# 1_energy_dist.net
KiCad netlist of a schematic drawn in EAGLE
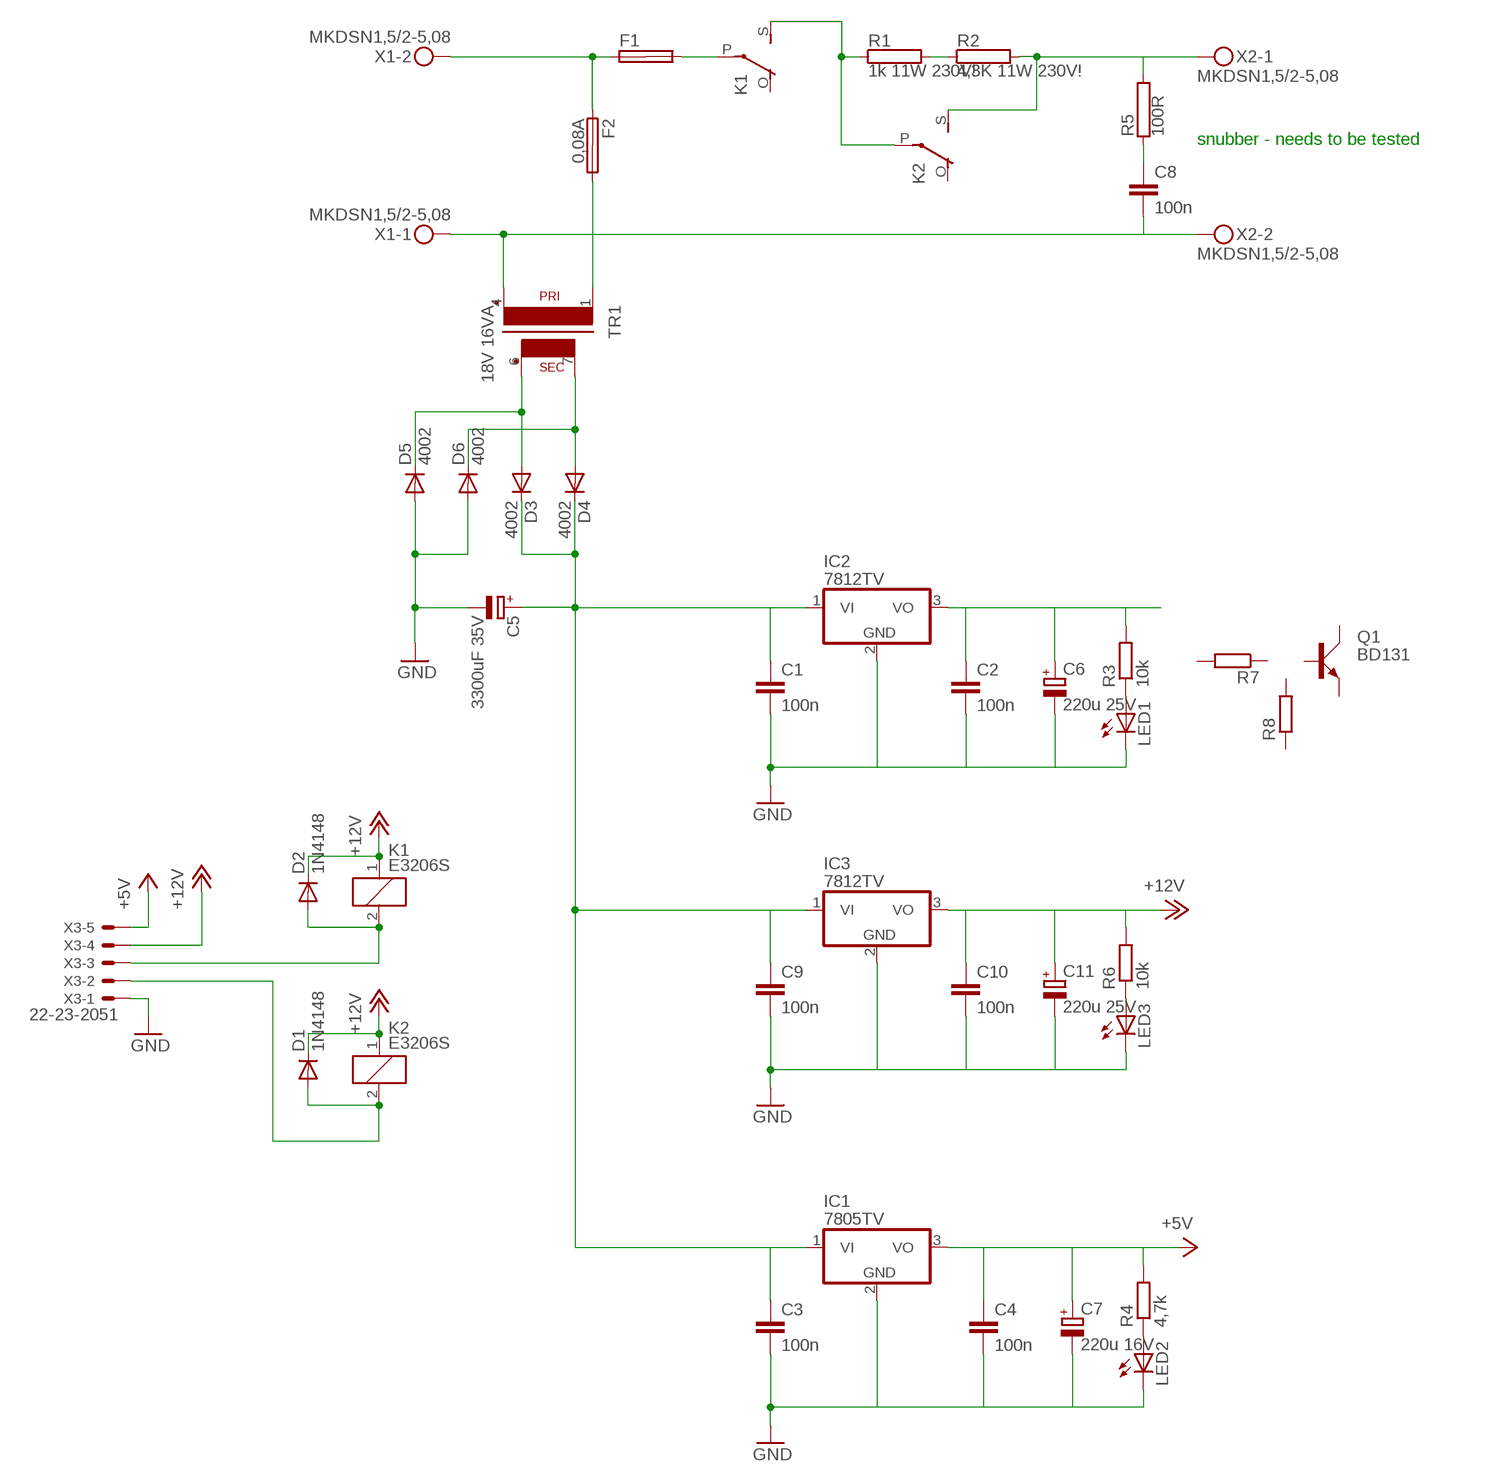
[diagram p0: schematic, sheet 1]

(export (version "E")
  (design (tool "Eeschema 10.0.6"))
  (components
    (comp (ref "C1")
      (value "100n")
      (footprint "eagle-import:C1206")
      (libsource (lib "eagle-import") (part "C-EUC1206"))
    )
    (comp (ref "C2")
      (value "100n")
      (footprint "eagle-import:C1206")
      (libsource (lib "eagle-import") (part "C-EUC1206"))
    )
    (comp (ref "C3")
      (value "100n")
      (footprint "eagle-import:C1206")
      (libsource (lib "eagle-import") (part "C-EUC1206"))
    )
    (comp (ref "C4")
      (value "100n")
      (footprint "eagle-import:C1206")
      (libsource (lib "eagle-import") (part "C-EUC1206"))
    )
    (comp (ref "C5")
      (value "3300uF 35V")
      (footprint "eagle-import:E7,5-16")
      (libsource (lib "eagle-import") (part "CPOL-EUE7.5-16"))
    )
    (comp (ref "C6")
      (value "220u 25V")
      (footprint "eagle-import:E7,5-16")
      (libsource (lib "eagle-import") (part "CPOL-EUE7.5-16"))
    )
    (comp (ref "C7")
      (value "220u 16V")
      (footprint "eagle-import:E7,5-16")
      (libsource (lib "eagle-import") (part "CPOL-EUE7.5-16"))
    )
    (comp (ref "C8")
      (value "100n")
      (footprint "eagle-import:C275-154X316")
      (libsource (lib "eagle-import") (part "C-EU275-154X316"))
    )
    (comp (ref "C9")
      (value "100n")
      (footprint "eagle-import:C1206")
      (libsource (lib "eagle-import") (part "C-EUC1206"))
    )
    (comp (ref "C10")
      (value "100n")
      (footprint "eagle-import:C1206")
      (libsource (lib "eagle-import") (part "C-EUC1206"))
    )
    (comp (ref "C11")
      (value "220u 25V")
      (footprint "eagle-import:E7,5-16")
      (libsource (lib "eagle-import") (part "CPOL-EUE7.5-16"))
    )
    (comp (ref "D1")
      (value "1N4148")
      (footprint "eagle-import:MELF-MLL41")
      (libsource (lib "eagle-import") (part "DIODE-MELF-MLL41"))
    )
    (comp (ref "D2")
      (value "1N4148")
      (footprint "eagle-import:MELF-MLL41")
      (libsource (lib "eagle-import") (part "DIODE-MELF-MLL41"))
    )
    (comp (ref "D3")
      (value "4002")
      (footprint "eagle-import:SOD-123_MINI-SMA")
      (libsource (lib "eagle-import") (part "CGRM400-G2"))
    )
    (comp (ref "D4")
      (value "4002")
      (footprint "eagle-import:SOD-123_MINI-SMA")
      (libsource (lib "eagle-import") (part "CGRM400-G2"))
    )
    (comp (ref "D5")
      (value "4002")
      (footprint "eagle-import:SOD-123_MINI-SMA")
      (libsource (lib "eagle-import") (part "CGRM400-G2"))
    )
    (comp (ref "D6")
      (value "4002")
      (footprint "eagle-import:SOD-123_MINI-SMA")
      (libsource (lib "eagle-import") (part "CGRM400-G2"))
    )
    (comp (ref "F1")
      (value "SH32")
      (footprint "eagle-import:SH32")
      (fields (field (name "MPN") "10207101009"))
      (libsource (lib "eagle-import") (part "SH32"))
    )
    (comp (ref "F2")
      (value "0,08A")
      (footprint "eagle-import:SH32")
      (fields (field (name "MPN") "10207101009"))
      (libsource (lib "eagle-import") (part "SH32"))
    )
    (comp (ref "IC1")
      (value "7805TV")
      (footprint "eagle-import:TO220V")
      (libsource (lib "eagle-import") (part "78TV05"))
    )
    (comp (ref "IC2")
      (value "7812TV")
      (footprint "eagle-import:TO220V")
      (libsource (lib "eagle-import") (part "78TV12"))
    )
    (comp (ref "IC3")
      (value "7812TV")
      (footprint "eagle-import:TO220V")
      (libsource (lib "eagle-import") (part "78TV12"))
    )
    (comp (ref "K1")
      (value "E3206S")
      (footprint "eagle-import:E3206S")
      (libsource (lib "eagle-import") (part "E3206S"))
    )
    (comp (ref "K2")
      (value "E3206S")
      (footprint "eagle-import:E3206S")
      (libsource (lib "eagle-import") (part "E3206S"))
    )
    (comp (ref "LED1")
      (value "LEDCHIPLED_1206")
      (footprint "eagle-import:CHIPLED_1206")
      (libsource (lib "eagle-import") (part "LEDCHIPLED_1206"))
    )
    (comp (ref "LED2")
      (value "LEDCHIPLED_1206")
      (footprint "eagle-import:CHIPLED_1206")
      (libsource (lib "eagle-import") (part "LEDCHIPLED_1206"))
    )
    (comp (ref "LED3")
      (value "LEDCHIPLED_1206")
      (footprint "eagle-import:CHIPLED_1206")
      (libsource (lib "eagle-import") (part "LEDCHIPLED_1206"))
    )
    (comp (ref "Q1")
      (value "BD131")
      (footprint "eagle-import:TO126AV")
      (libsource (lib "eagle-import") (part "BD139"))
    )
    (comp (ref "R1")
      (value "1k 11W 230V!")
      (footprint "eagle-import:KH216-8")
      (libsource (lib "eagle-import") (part "RKH216-8"))
    )
    (comp (ref "R2")
      (value "4,3K 11W 230V!")
      (footprint "eagle-import:KH216-8")
      (libsource (lib "eagle-import") (part "RKH216-8"))
    )
    (comp (ref "R3")
      (value "10k")
      (footprint "eagle-import:M1206")
      (libsource (lib "eagle-import") (part "R-EU_M1206"))
    )
    (comp (ref "R4")
      (value "4,7k")
      (footprint "eagle-import:M1206")
      (libsource (lib "eagle-import") (part "R-EU_M1206"))
    )
    (comp (ref "R5")
      (value "100R")
      (footprint "eagle-import:CA0001")
      (libsource (lib "eagle-import") (part "RCA0001"))
    )
    (comp (ref "R6")
      (value "10k")
      (footprint "eagle-import:M1206")
      (libsource (lib "eagle-import") (part "R-EU_M1206"))
    )
    (comp (ref "R7")
      (value "R-EU_M1206")
      (footprint "eagle-import:M1206")
      (libsource (lib "eagle-import") (part "R-EU_M1206"))
    )
    (comp (ref "R8")
      (value "R-EU_M1206")
      (footprint "eagle-import:M1206")
      (libsource (lib "eagle-import") (part "R-EU_M1206"))
    )
    (comp (ref "TR1")
      (value "18V 16VA")
      (footprint "eagle-import:EE20-1")
      (libsource (lib "eagle-import") (part "EE20-1"))
    )
    (comp (ref "X1")
      (value "MKDSN1,5/2-5,08")
      (footprint "eagle-import:MKDSN1,5_2-5,08")
      (libsource (lib "eagle-import") (part "MKDSN1,5/2-5,08"))
    )
    (comp (ref "X2")
      (value "MKDSN1,5/2-5,08")
      (footprint "eagle-import:MKDSN1,5_2-5,08")
      (libsource (lib "eagle-import") (part "MKDSN1,5/2-5,08"))
    )
    (comp (ref "X3")
      (value "22-23-2051")
      (footprint "eagle-import:22-23-2051")
      (fields (field (name "MF") "MOLEX"))
      (libsource (lib "eagle-import") (part "22-23-2051"))
    )
  )
  (nets
    (net (code "1") (name "+5V") (class "Default")
      (node (ref "C4") (pin "1") (pinfunction "1_1") (pintype "passive"))
      (node (ref "C7") (pin "+") (pinfunction "+_+") (pintype "passive"))
      (node (ref "IC1") (pin "3") (pinfunction "VO_3") (pintype "passive"))
      (node (ref "R4") (pin "2") (pinfunction "2_2") (pintype "passive"))
      (node (ref "X3") (pin "5") (pinfunction "S_5") (pintype "passive"))
    )
    (net (code "2") (name "+12V") (class "Default")
      (node (ref "C10") (pin "1") (pinfunction "1_1") (pintype "passive"))
      (node (ref "C11") (pin "+") (pinfunction "+_+") (pintype "passive"))
      (node (ref "D1") (pin "C") (pinfunction "C_C") (pintype "passive"))
      (node (ref "D2") (pin "C") (pinfunction "C_C") (pintype "passive"))
      (node (ref "IC3") (pin "3") (pinfunction "VO_3") (pintype "passive"))
      (node (ref "K1") (pin "1") (pinfunction "1_1") (pintype "passive"))
      (node (ref "K2") (pin "1") (pinfunction "1_1") (pintype "passive"))
      (node (ref "R6") (pin "2") (pinfunction "2_2") (pintype "passive"))
      (node (ref "X3") (pin "4") (pinfunction "S_4") (pintype "passive"))
    )
    (net (code "3") (name "GND") (class "Default")
      (node (ref "C1") (pin "2") (pinfunction "2_2") (pintype "passive"))
      (node (ref "C10") (pin "2") (pinfunction "2_2") (pintype "passive"))
      (node (ref "C11") (pin "-") (pinfunction "-_-") (pintype "passive"))
      (node (ref "C2") (pin "2") (pinfunction "2_2") (pintype "passive"))
      (node (ref "C3") (pin "2") (pinfunction "2_2") (pintype "passive"))
      (node (ref "C4") (pin "2") (pinfunction "2_2") (pintype "passive"))
      (node (ref "C5") (pin "-") (pinfunction "-_-") (pintype "passive"))
      (node (ref "C6") (pin "-") (pinfunction "-_-") (pintype "passive"))
      (node (ref "C7") (pin "-") (pinfunction "-_-") (pintype "passive"))
      (node (ref "C9") (pin "2") (pinfunction "2_2") (pintype "passive"))
      (node (ref "D5") (pin "A") (pinfunction "A_A") (pintype "passive"))
      (node (ref "D6") (pin "A") (pinfunction "A_A") (pintype "passive"))
      (node (ref "IC1") (pin "2") (pinfunction "GND_2") (pintype "passive"))
      (node (ref "IC2") (pin "2") (pinfunction "GND_2") (pintype "passive"))
      (node (ref "IC3") (pin "2") (pinfunction "GND_2") (pintype "passive"))
      (node (ref "LED1") (pin "C") (pinfunction "C_C") (pintype "passive"))
      (node (ref "LED2") (pin "C") (pinfunction "C_C") (pintype "passive"))
      (node (ref "LED3") (pin "C") (pinfunction "C_C") (pintype "passive"))
      (node (ref "X3") (pin "1") (pinfunction "S_1") (pintype "passive"))
    )
    (net (code "4") (name "Net-(C8-Pad1)") (class "Default")
      (node (ref "C8") (pin "1") (pinfunction "1_1") (pintype "passive"))
      (node (ref "R5") (pin "1") (pinfunction "1_1") (pintype "passive"))
    )
    (net (code "5") (name "Net-(F1-Pad2A)") (class "Default")
      (node (ref "F1") (pin "2A") (pinfunction "2A_2A") (pintype "passive"))
      (node (ref "K1") (pin "P") (pinfunction "P_P") (pintype "passive"))
    )
    (net (code "6") (name "Net-(IC1-VI)") (class "Default")
      (node (ref "C1") (pin "1") (pinfunction "1_1") (pintype "passive"))
      (node (ref "C3") (pin "1") (pinfunction "1_1") (pintype "passive"))
      (node (ref "C5") (pin "+") (pinfunction "+_+") (pintype "passive"))
      (node (ref "C9") (pin "1") (pinfunction "1_1") (pintype "passive"))
      (node (ref "D3") (pin "C") (pinfunction "C_C") (pintype "passive"))
      (node (ref "D4") (pin "C") (pinfunction "C_C") (pintype "passive"))
      (node (ref "IC1") (pin "1") (pinfunction "VI_1") (pintype "input"))
      (node (ref "IC2") (pin "1") (pinfunction "VI_1") (pintype "input"))
      (node (ref "IC3") (pin "1") (pinfunction "VI_1") (pintype "input"))
    )
    (net (code "7") (name "Net-(IC2-VO)") (class "Default")
      (node (ref "C2") (pin "1") (pinfunction "1_1") (pintype "passive"))
      (node (ref "C6") (pin "+") (pinfunction "+_+") (pintype "passive"))
      (node (ref "IC2") (pin "3") (pinfunction "VO_3") (pintype "passive"))
      (node (ref "R3") (pin "2") (pinfunction "2_2") (pintype "passive"))
    )
    (net (code "8") (name "Net-(K1-PadS)") (class "Default")
      (node (ref "K1") (pin "S") (pinfunction "S_S") (pintype "passive"))
      (node (ref "K2") (pin "P") (pinfunction "P_P") (pintype "passive"))
      (node (ref "R1") (pin "1") (pinfunction "1_1") (pintype "passive"))
    )
    (net (code "9") (name "Net-(LED1-PadA)") (class "Default")
      (node (ref "LED1") (pin "A") (pinfunction "A_A") (pintype "passive"))
      (node (ref "R3") (pin "1") (pinfunction "1_1") (pintype "passive"))
    )
    (net (code "10") (name "Net-(LED2-PadA)") (class "Default")
      (node (ref "LED2") (pin "A") (pinfunction "A_A") (pintype "passive"))
      (node (ref "R4") (pin "1") (pinfunction "1_1") (pintype "passive"))
    )
    (net (code "11") (name "Net-(LED3-PadA)") (class "Default")
      (node (ref "LED3") (pin "A") (pinfunction "A_A") (pintype "passive"))
      (node (ref "R6") (pin "1") (pinfunction "1_1") (pintype "passive"))
    )
    (net (code "12") (name "Net-(R1-Pad2)") (class "Default")
      (node (ref "R1") (pin "2") (pinfunction "2_2") (pintype "passive"))
      (node (ref "R2") (pin "1") (pinfunction "1_1") (pintype "passive"))
    )
    (net (code "13") (name "Net-(TR1-P1)") (class "Default")
      (node (ref "F2") (pin "2A") (pinfunction "2A_2A") (pintype "passive"))
      (node (ref "TR1") (pin "1") (pinfunction "P1_1") (pintype "passive"))
    )
    (net (code "14") (name "Net-(TR1-P2)") (class "Default")
      (node (ref "C8") (pin "2") (pinfunction "2_2") (pintype "passive"))
      (node (ref "TR1") (pin "4") (pinfunction "P2_4") (pintype "passive"))
      (node (ref "X1") (pin "1") (pinfunction "KL_1") (pintype "passive"))
      (node (ref "X2") (pin "2") (pinfunction "KL_2") (pintype "passive"))
    )
    (net (code "15") (name "Net-(TR1-S3)") (class "Default")
      (node (ref "D3") (pin "A") (pinfunction "A_A") (pintype "passive"))
      (node (ref "D5") (pin "C") (pinfunction "C_C") (pintype "passive"))
      (node (ref "TR1") (pin "6") (pinfunction "S3_6") (pintype "passive"))
    )
    (net (code "16") (name "Net-(TR1-S4)") (class "Default")
      (node (ref "D4") (pin "A") (pinfunction "A_A") (pintype "passive"))
      (node (ref "D6") (pin "C") (pinfunction "C_C") (pintype "passive"))
      (node (ref "TR1") (pin "7") (pinfunction "S4_7") (pintype "passive"))
    )
    (net (code "17") (name "Net-(X1B-KL)") (class "Default")
      (node (ref "F1") (pin "1A") (pinfunction "1A_1A") (pintype "passive"))
      (node (ref "F2") (pin "1A") (pinfunction "1A_1A") (pintype "passive"))
      (node (ref "X1") (pin "2") (pinfunction "KL_2") (pintype "passive"))
    )
    (net (code "18") (name "Net-(X2A-KL)") (class "Default")
      (node (ref "K2") (pin "S") (pinfunction "S_S") (pintype "passive"))
      (node (ref "R2") (pin "2") (pinfunction "2_2") (pintype "passive"))
      (node (ref "R5") (pin "2") (pinfunction "2_2") (pintype "passive"))
      (node (ref "X2") (pin "1") (pinfunction "KL_1") (pintype "passive"))
    )
    (net (code "19") (name "Net-(X3B-S)") (class "Default")
      (node (ref "D1") (pin "A") (pinfunction "A_A") (pintype "passive"))
      (node (ref "K2") (pin "2") (pinfunction "2_2") (pintype "passive"))
      (node (ref "X3") (pin "2") (pinfunction "S_2") (pintype "passive"))
    )
    (net (code "20") (name "Net-(X3C-S)") (class "Default")
      (node (ref "D2") (pin "A") (pinfunction "A_A") (pintype "passive"))
      (node (ref "K1") (pin "2") (pinfunction "2_2") (pintype "passive"))
      (node (ref "X3") (pin "3") (pinfunction "S_3") (pintype "passive"))
    )
    (net (code "21") (name "unconnected-(F1-Pad1B)") (class "Default")
      (node (ref "F1") (pin "1B") (pinfunction "1B_1B") (pintype "passive"))
    )
    (net (code "22") (name "unconnected-(F1-Pad2B)") (class "Default")
      (node (ref "F1") (pin "2B") (pinfunction "2B_2B") (pintype "passive"))
    )
    (net (code "23") (name "unconnected-(F2-Pad1B)") (class "Default")
      (node (ref "F2") (pin "1B") (pinfunction "1B_1B") (pintype "passive"))
    )
    (net (code "24") (name "unconnected-(F2-Pad2B)") (class "Default")
      (node (ref "F2") (pin "2B") (pinfunction "2B_2B") (pintype "passive"))
    )
    (net (code "25") (name "unconnected-(K1-PadO)") (class "Default")
      (node (ref "K1") (pin "O") (pinfunction "O_O") (pintype "passive"))
    )
    (net (code "26") (name "unconnected-(K2-PadO)") (class "Default")
      (node (ref "K2") (pin "O") (pinfunction "O_O") (pintype "passive"))
    )
    (net (code "27") (name "unconnected-(Q1-PadB)") (class "Default")
      (node (ref "Q1") (pin "B") (pinfunction "B_B") (pintype "passive"))
    )
    (net (code "28") (name "unconnected-(Q1-PadC)") (class "Default")
      (node (ref "Q1") (pin "C") (pinfunction "C_C") (pintype "passive"))
    )
    (net (code "29") (name "unconnected-(Q1-PadE)") (class "Default")
      (node (ref "Q1") (pin "E") (pinfunction "E_E") (pintype "passive"))
    )
    (net (code "30") (name "unconnected-(R7-Pad1)") (class "Default")
      (node (ref "R7") (pin "1") (pinfunction "1_1") (pintype "passive"))
    )
    (net (code "31") (name "unconnected-(R7-Pad2)") (class "Default")
      (node (ref "R7") (pin "2") (pinfunction "2_2") (pintype "passive"))
    )
    (net (code "32") (name "unconnected-(R8-Pad1)") (class "Default")
      (node (ref "R8") (pin "1") (pinfunction "1_1") (pintype "passive"))
    )
    (net (code "33") (name "unconnected-(R8-Pad2)") (class "Default")
      (node (ref "R8") (pin "2") (pinfunction "2_2") (pintype "passive"))
    )
  )
)
